# butt-on-mk-1_0.net
KiCad netlist of a schematic drawn in EAGLE
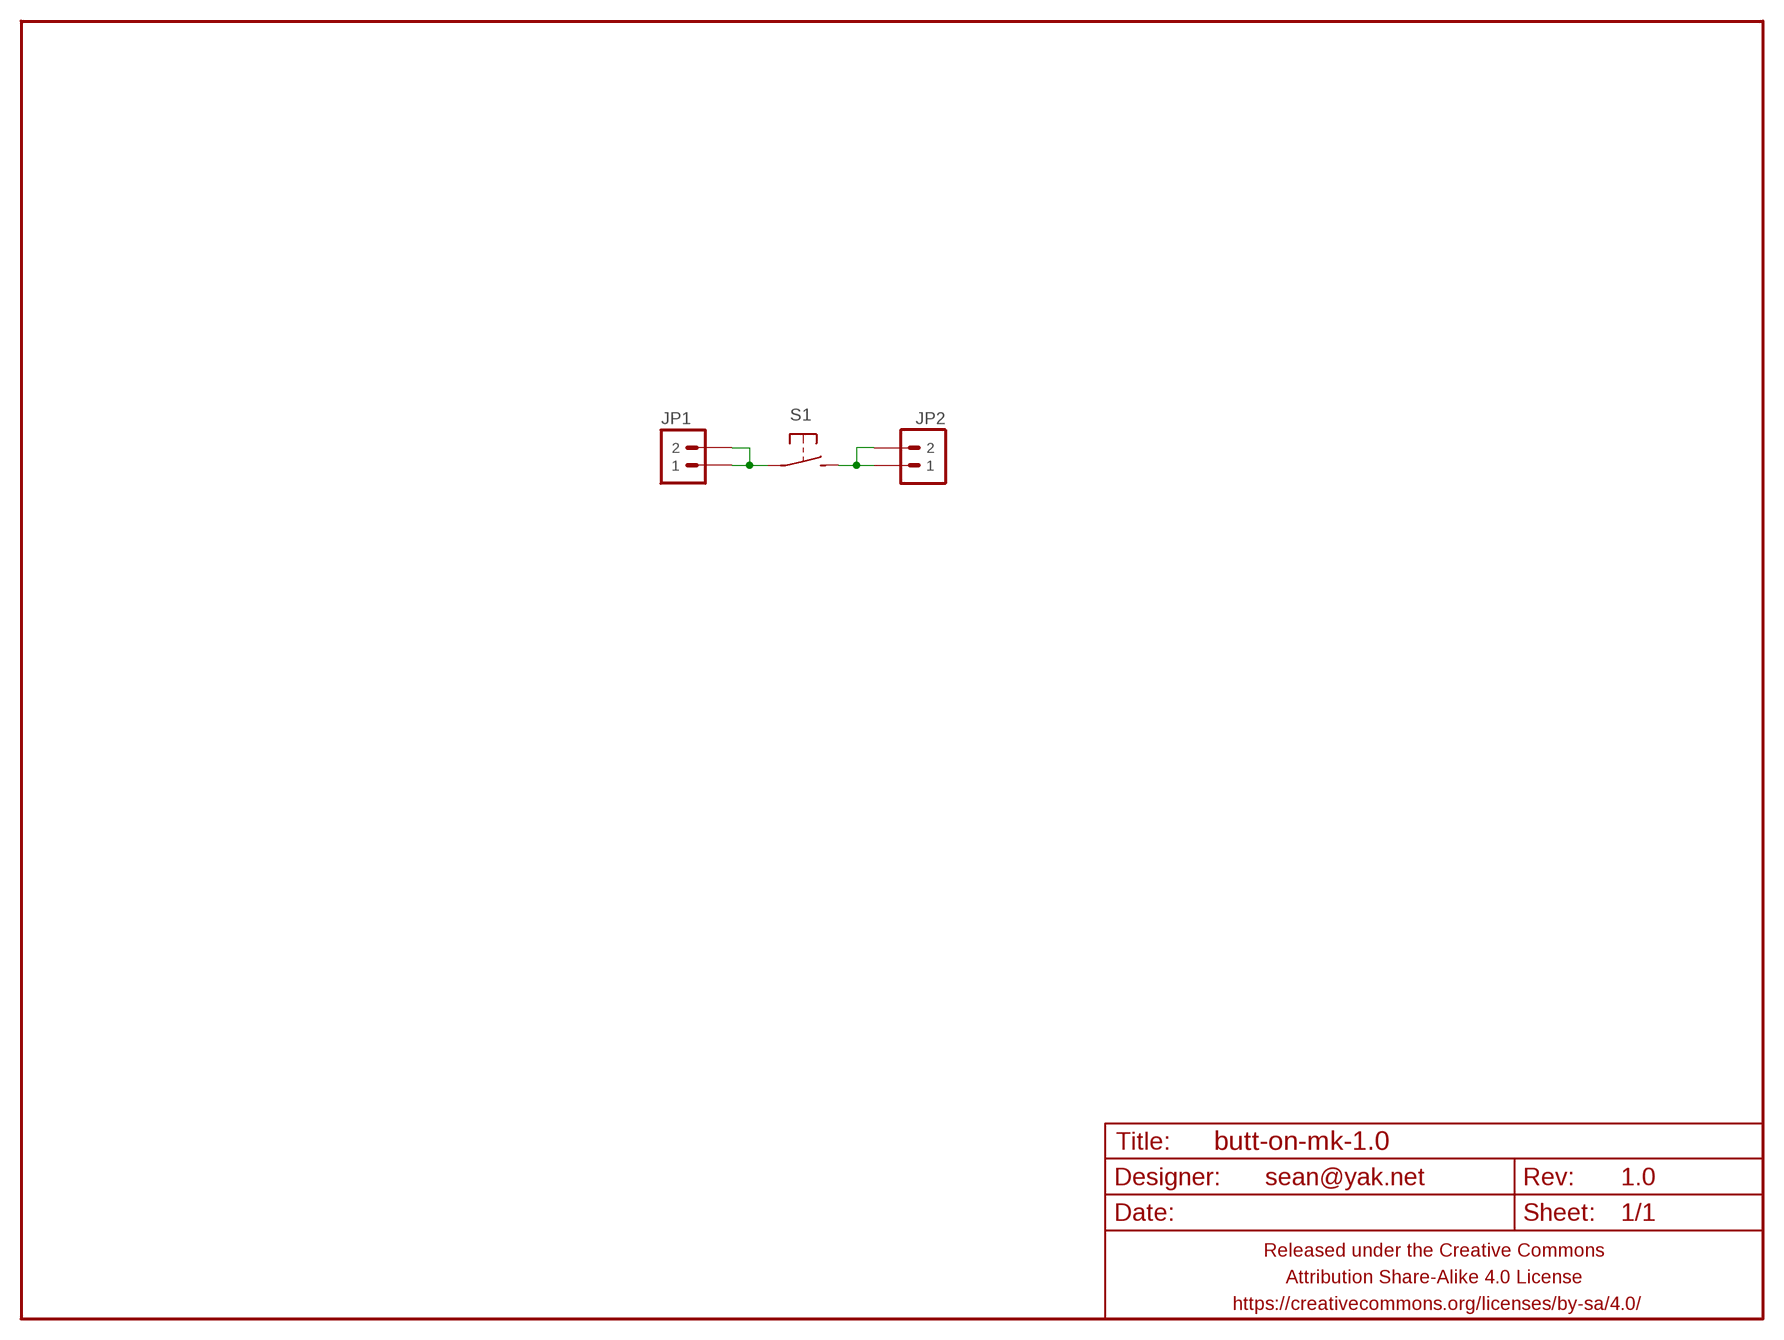
[diagram p0: schematic, sheet 1]

(export (version "E")
  (design (tool "Eeschema 10.0.6"))
  (components
    (comp (ref "FRAME1")
      (value "FRAME-LETTERNO_PACKAGE")
      (footprint "eagle-import:DUMMY")
      (fields (field (name "DESIGNER") "sean@yak.net") (field (name "VERSION") "1.0"))
      (libsource (lib "eagle-import") (part "FRAME-LETTERNO_PACKAGE"))
    )
    (comp (ref "JP1")
      (value "M02PTH-CENTERED")
      (footprint "eagle-import:1X02-CENTER")
      (libsource (lib "eagle-import") (part "M02PTH-CENTERED"))
    )
    (comp (ref "JP2")
      (value "M02PTH-CENTERED")
      (footprint "eagle-import:1X02-CENTER")
      (libsource (lib "eagle-import") (part "M02PTH-CENTERED"))
    )
    (comp (ref "S1")
      (value "SPST-NO-TACT3MM-PTH-SMALL-PADS")
      (footprint "eagle-import:DTS-3-SMALL-PADS")
      (libsource (lib "eagle-import") (part "SPST-NO-TACT3MM-PTH-SMALL-PADS"))
    )
  )
  (nets
    (net (code "1") (name "Net-(JP1-Pad1)") (class "Default")
      (node (ref "JP1") (pin "1") (pinfunction "1_1") (pintype "passive"))
      (node (ref "JP1") (pin "2") (pinfunction "2_2") (pintype "passive"))
      (node (ref "S1") (pin "1") (pinfunction "1_1") (pintype "passive"))
    )
    (net (code "2") (name "Net-(JP2-Pad1)") (class "Default")
      (node (ref "JP2") (pin "1") (pinfunction "1_1") (pintype "passive"))
      (node (ref "JP2") (pin "2") (pinfunction "2_2") (pintype "passive"))
      (node (ref "S1") (pin "2") (pinfunction "2_2") (pintype "passive"))
    )
  )
)
